# MCU.net
KiCad netlist of a schematic drawn in Altium Designer
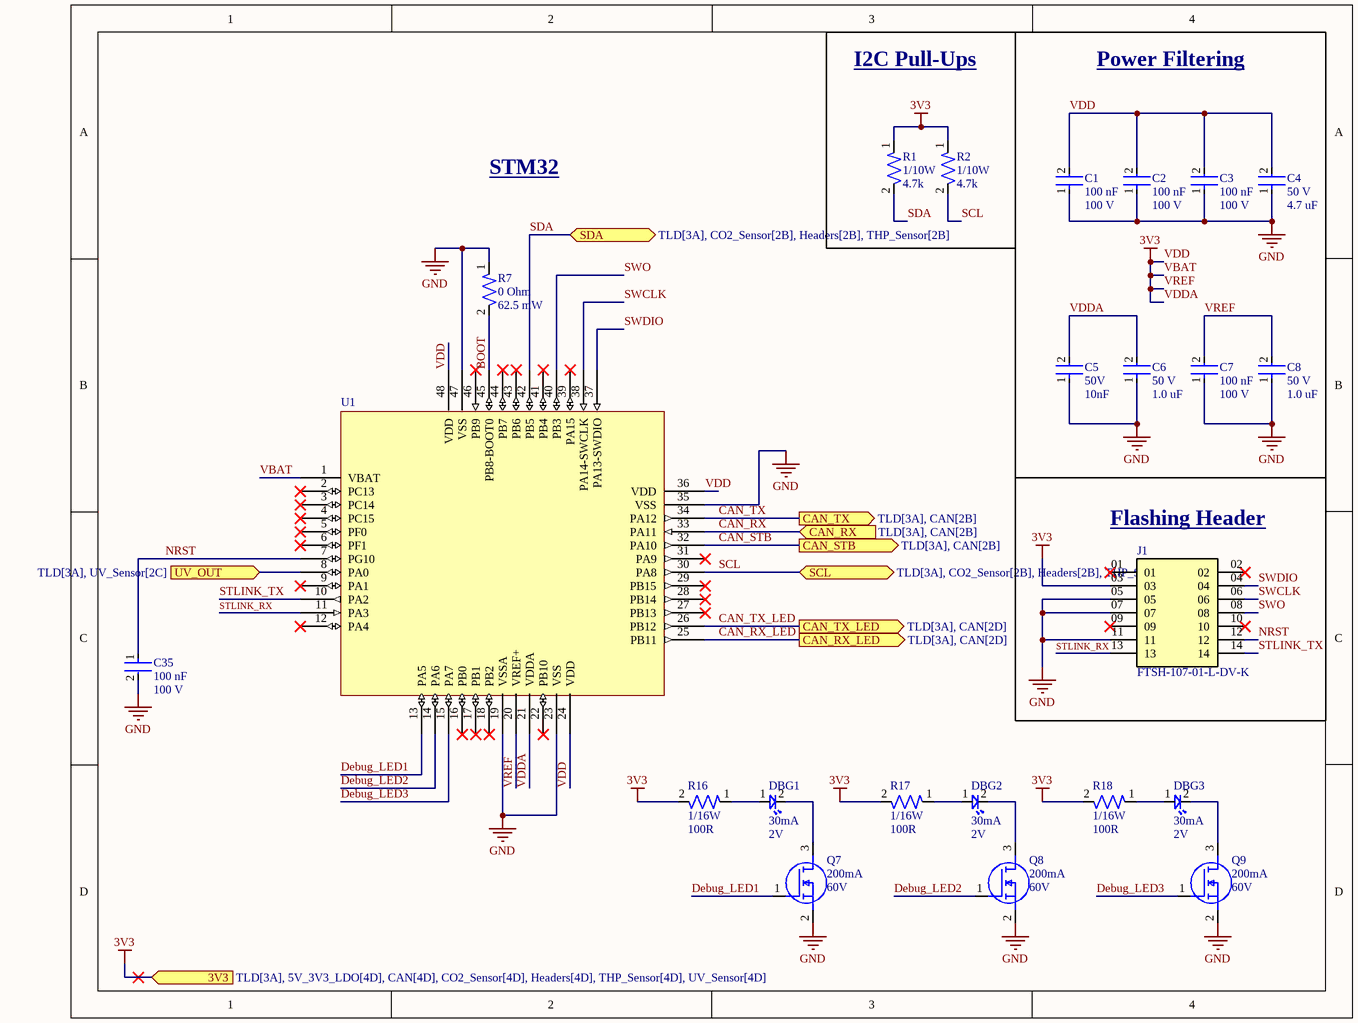
[diagram p0: MCU.SchDoc]

(export (version "E")
  (design (tool "Eeschema 10.0.6"))
  (components
    (comp (ref "C1")
      (value "CC0603KRX7R0BB104")
      (footprint "CAP-0603")
      (description "CAP CER 0.1UF 100V X7R 0603")
      (fields (field (name "CAPACITANCE") "100 nF") (field (name "VOLTAGE") "100 V"))
      (libsource (lib "JLC_25") (part "CAP-100N-0001"))
    )
    (comp (ref "C2")
      (value "CC0603KRX7R0BB104")
      (footprint "CAP-0603")
      (description "CAP CER 0.1UF 100V X7R 0603")
      (fields (field (name "CAPACITANCE") "100 nF") (field (name "VOLTAGE") "100 V"))
      (libsource (lib "JLC_25") (part "CAP-100N-0001"))
    )
    (comp (ref "C3")
      (value "CC0603KRX7R0BB104")
      (footprint "CAP-0603")
      (description "CAP CER 0.1UF 100V X7R 0603")
      (fields (field (name "CAPACITANCE") "100 nF") (field (name "VOLTAGE") "100 V"))
      (libsource (lib "JLC_25") (part "CAP-100N-0001"))
    )
    (comp (ref "C4")
      (value "CC0805KKX5R9BB475")
      (footprint "CAP-0805")
      (description "CAP CER 4.7UF 50V X5R 0805")
      (fields (field (name "VOLTAGE") "50 V") (field (name "CAPACITANCE") "4.7 uF"))
      (libsource (lib "JLC_25") (part "CAP-4.7U-0002"))
    )
    (comp (ref "C5")
      (value "GRM2195C1H103JA01D")
      (footprint "CAP-0805")
      (description "CAP CER 10000PF 50V C0G/NP0 0805")
      (fields (field (name "VOLTAGE") "50V") (field (name "CAPACITANCE") "10nF"))
      (libsource (lib "JLC_25") (part "CAP-10N-0001"))
    )
    (comp (ref "C6")
      (value "CC0805KKX7R9BB105")
      (footprint "CAP-0805")
      (description "CAP CER 1UF 50V X7R 0805")
      (fields (field (name "VOLTAGE") "50 V") (field (name "CAPACITANCE") "1.0 uF"))
      (libsource (lib "JLC_25") (part "CAP-1U-0001"))
    )
    (comp (ref "C7")
      (value "CC0603KRX7R0BB104")
      (footprint "CAP-0603")
      (description "CAP CER 0.1UF 100V X7R 0603")
      (fields (field (name "CAPACITANCE") "100 nF") (field (name "VOLTAGE") "100 V"))
      (libsource (lib "JLC_25") (part "CAP-100N-0001"))
    )
    (comp (ref "C8")
      (value "CC0805KKX7R9BB105")
      (footprint "CAP-0805")
      (description "CAP CER 1UF 50V X7R 0805")
      (fields (field (name "VOLTAGE") "50 V") (field (name "CAPACITANCE") "1.0 uF"))
      (libsource (lib "JLC_25") (part "CAP-1U-0001"))
    )
    (comp (ref "C35")
      (value "CC0603KRX7R0BB104")
      (footprint "CAP-0603")
      (description "CAP CER 0.1UF 100V X7R 0603")
      (fields (field (name "CAPACITANCE") "100 nF") (field (name "VOLTAGE") "100 V"))
      (libsource (lib "JLC_25") (part "CAP-100N-0001"))
    )
    (comp (ref "DBG1")
      (value "BL-HKC36G-AV-TRB")
      (footprint "LED-0603")
      (description "LED YELLOW CLEAR 0603 SMD")
      (fields (field (name "FORWARD CURRENT") "30mA") (field (name "FORWARD VOLTAGE") "2V"))
      (libsource (lib "JLC_25") (part "LED-0001"))
    )
    (comp (ref "DBG2")
      (value "BL-HKC36G-AV-TRB")
      (footprint "LED-0603")
      (description "LED YELLOW CLEAR 0603 SMD")
      (fields (field (name "FORWARD CURRENT") "30mA") (field (name "FORWARD VOLTAGE") "2V"))
      (libsource (lib "JLC_25") (part "LED-0001"))
    )
    (comp (ref "DBG3")
      (value "BL-HKC36G-AV-TRB")
      (footprint "LED-0603")
      (description "LED YELLOW CLEAR 0603 SMD")
      (fields (field (name "FORWARD CURRENT") "30mA") (field (name "FORWARD VOLTAGE") "2V"))
      (libsource (lib "JLC_25") (part "LED-0001"))
    )
    (comp (ref "J1")
      (value "FTSH-107-01-L-DV-K")
      (footprint "SAMTEC_FTSH-107-01-L-DV-K")
      (description "Connector Header Surface Mount 14 position 0.050\" (1.27mm)")
      (fields (field (name "MF") "Samtec"))
      (libsource (lib "MasterLib") (part "CONN_Flashing-0001"))
    )
    (comp (ref "Q7")
      (value "T2N7002AK,LM")
      (footprint "IC-SOT23-3")
      (description "MOSFET N-CH 60V 200MA SOT23")
      (fields (field (name "CONTINUOUS CURRENT") "200mA") (field (name "VOLTAGE") "60V"))
      (libsource (lib "JLC_25") (part "NMOS-200MA-0001"))
    )
    (comp (ref "Q8")
      (value "T2N7002AK,LM")
      (footprint "IC-SOT23-3")
      (description "MOSFET N-CH 60V 200MA SOT23")
      (fields (field (name "CONTINUOUS CURRENT") "200mA") (field (name "VOLTAGE") "60V"))
      (libsource (lib "JLC_25") (part "NMOS-200MA-0001"))
    )
    (comp (ref "Q9")
      (value "T2N7002AK,LM")
      (footprint "IC-SOT23-3")
      (description "MOSFET N-CH 60V 200MA SOT23")
      (fields (field (name "CONTINUOUS CURRENT") "200mA") (field (name "VOLTAGE") "60V"))
      (libsource (lib "JLC_25") (part "NMOS-200MA-0001"))
    )
    (comp (ref "R1")
      (value "RC0603FR-074K7L")
      (footprint "RES-0603")
      (description "RES 4.7K OHM 1% 1/10W 0603")
      (fields
        (field (name "TOLERANCE") "1%")
        (field (name "POWER") "1/10W")
        (field (name "RESISTANCE") "4.7k")
      )
      (libsource (lib "JLC_25") (part "RES-4.7k-0001"))
    )
    (comp (ref "R2")
      (value "RC0603FR-074K7L")
      (footprint "RES-0603")
      (description "RES 4.7K OHM 1% 1/10W 0603")
      (fields
        (field (name "TOLERANCE") "1%")
        (field (name "POWER") "1/10W")
        (field (name "RESISTANCE") "4.7k")
      )
      (libsource (lib "JLC_25") (part "RES-4.7k-0001"))
    )
    (comp (ref "R7")
      (value "RC0402FR-070RL")
      (footprint "RES-0402")
      (description "62.5mW Thick Film Resistors 50V -55℃~+155℃ 0Ω 0402 Chip Resistor - Surface Mount ROHS")
      (fields
        (field (name "JLC PART NUMBER") "C106231")
        (field (name "RESISTANCE") "0 Ohm")
        (field (name "POWER") "62.5 mW")
      )
      (libsource (lib "MasterLib") (part "RES-0-0002-JLC"))
    )
    (comp (ref "R16")
      (value "RC0402FR-07100RL")
      (footprint "RES-0402")
      (description "RES 100 OHM 1% 1/16W 0402")
      (fields
        (field (name "TOLERANCE") "1%")
        (field (name "POWER") "1/16W")
        (field (name "RESISTANCE") "100R")
      )
      (libsource (lib "JLC_25") (part "RES-100-0001"))
    )
    (comp (ref "R17")
      (value "RC0402FR-07100RL")
      (footprint "RES-0402")
      (description "RES 100 OHM 1% 1/16W 0402")
      (fields
        (field (name "TOLERANCE") "1%")
        (field (name "POWER") "1/16W")
        (field (name "RESISTANCE") "100R")
      )
      (libsource (lib "JLC_25") (part "RES-100-0001"))
    )
    (comp (ref "R18")
      (value "RC0402FR-07100RL")
      (footprint "RES-0402")
      (description "RES 100 OHM 1% 1/16W 0402")
      (fields
        (field (name "TOLERANCE") "1%")
        (field (name "POWER") "1/16W")
        (field (name "RESISTANCE") "100R")
      )
      (libsource (lib "JLC_25") (part "RES-100-0001"))
    )
    (comp (ref "U1")
      (value "STM32G431CBT6")
      (footprint "IC-LQFP48")
      (description "IC MCU 32BIT 128KB FLASH 48LQFP")
      (libsource (lib "JLC_25") (part "IC-STM32G431CBT6"))
    )
  )
  (nets
    (net (code "1") (name "/BOOT") (class "Default")
      (node (ref "R7") (pin "2") (pinfunction "2_2") (pintype "passive"))
      (node (ref "U1") (pin "45") (pinfunction "PB8-BOOT0_45") (pintype "bidirectional"))
    )
    (net (code "2") (name "/CAN_RX") (class "Default")
      (node (ref "U1") (pin "33") (pinfunction "PA11_33") (pintype "input"))
    )
    (net (code "3") (name "/CAN_RX_LED") (class "Default")
      (node (ref "U1") (pin "25") (pinfunction "PB11_25") (pintype "output"))
    )
    (net (code "4") (name "/CAN_STB") (class "Default")
      (node (ref "U1") (pin "32") (pinfunction "PA10_32") (pintype "output"))
    )
    (net (code "5") (name "/CAN_TX") (class "Default")
      (node (ref "U1") (pin "34") (pinfunction "PA12_34") (pintype "output"))
    )
    (net (code "6") (name "/CAN_TX_LED") (class "Default")
      (node (ref "U1") (pin "26") (pinfunction "PB12_26") (pintype "output"))
    )
    (net (code "7") (name "/Debug_LED1") (class "Default")
      (node (ref "Q7") (pin "1") (pinfunction "G_1") (pintype "passive"))
      (node (ref "U1") (pin "13") (pinfunction "PA5_13") (pintype "bidirectional"))
    )
    (net (code "8") (name "/Debug_LED2") (class "Default")
      (node (ref "Q8") (pin "1") (pinfunction "G_1") (pintype "passive"))
      (node (ref "U1") (pin "14") (pinfunction "PA6_14") (pintype "bidirectional"))
    )
    (net (code "9") (name "/Debug_LED3") (class "Default")
      (node (ref "Q9") (pin "1") (pinfunction "G_1") (pintype "passive"))
      (node (ref "U1") (pin "15") (pinfunction "PA7_15") (pintype "bidirectional"))
    )
    (net (code "10") (name "/NRST") (class "Default")
      (node (ref "C35") (pin "1") (pinfunction "1_1") (pintype "passive"))
      (node (ref "J1") (pin "12") (pinfunction "12_12") (pintype "passive"))
      (node (ref "U1") (pin "7") (pinfunction "PG10_7") (pintype "bidirectional"))
    )
    (net (code "11") (name "/SCL") (class "Default")
      (node (ref "R2") (pin "2") (pinfunction "2_2") (pintype "passive"))
      (node (ref "U1") (pin "30") (pinfunction "PA8_30") (pintype "output"))
    )
    (net (code "12") (name "/SDA") (class "Default")
      (node (ref "R1") (pin "2") (pinfunction "2_2") (pintype "passive"))
      (node (ref "U1") (pin "42") (pinfunction "PB5_42") (pintype "bidirectional"))
    )
    (net (code "13") (name "/STLINK_RX") (class "Default")
      (node (ref "J1") (pin "13") (pinfunction "13_13") (pintype "passive"))
      (node (ref "U1") (pin "11") (pinfunction "PA3_11") (pintype "input"))
    )
    (net (code "14") (name "/STLINK_TX") (class "Default")
      (node (ref "J1") (pin "14") (pinfunction "14_14") (pintype "passive"))
      (node (ref "U1") (pin "10") (pinfunction "PA2_10") (pintype "output"))
    )
    (net (code "15") (name "/SWCLK") (class "Default")
      (node (ref "J1") (pin "06") (pinfunction "06_06") (pintype "passive"))
      (node (ref "U1") (pin "38") (pinfunction "PA14-SWCLK_38") (pintype "input"))
    )
    (net (code "16") (name "/SWDIO") (class "Default")
      (node (ref "J1") (pin "04") (pinfunction "04_04") (pintype "passive"))
      (node (ref "U1") (pin "37") (pinfunction "PA13-SWDIO_37") (pintype "input"))
    )
    (net (code "17") (name "/SWO") (class "Default")
      (node (ref "J1") (pin "08") (pinfunction "08_08") (pintype "passive"))
      (node (ref "U1") (pin "40") (pinfunction "PB3_40") (pintype "bidirectional"))
    )
    (net (code "18") (name "/UV_OUT") (class "Default")
      (node (ref "U1") (pin "8") (pinfunction "PA0_8") (pintype "bidirectional"))
    )
    (net (code "19") (name "3V3") (class "Default")
      (node (ref "C1") (pin "2") (pinfunction "2_2") (pintype "passive"))
      (node (ref "C2") (pin "2") (pinfunction "2_2") (pintype "passive"))
      (node (ref "C3") (pin "2") (pinfunction "2_2") (pintype "passive"))
      (node (ref "C4") (pin "2") (pinfunction "2_2") (pintype "passive"))
      (node (ref "C5") (pin "2") (pinfunction "2_2") (pintype "passive"))
      (node (ref "C6") (pin "2") (pinfunction "2_2") (pintype "passive"))
      (node (ref "C7") (pin "2") (pinfunction "2_2") (pintype "passive"))
      (node (ref "C8") (pin "2") (pinfunction "2_2") (pintype "passive"))
      (node (ref "J1") (pin "03") (pinfunction "03_03") (pintype "passive"))
      (node (ref "R1") (pin "1") (pinfunction "1_1") (pintype "passive"))
      (node (ref "R16") (pin "2") (pinfunction "2_2") (pintype "passive"))
      (node (ref "R17") (pin "2") (pinfunction "2_2") (pintype "passive"))
      (node (ref "R18") (pin "2") (pinfunction "2_2") (pintype "passive"))
      (node (ref "R2") (pin "1") (pinfunction "1_1") (pintype "passive"))
      (node (ref "U1") (pin "1") (pinfunction "VBAT_1") (pintype "power_in"))
      (node (ref "U1") (pin "20") (pinfunction "VREF+_20") (pintype "power_in"))
      (node (ref "U1") (pin "21") (pinfunction "VDDA_21") (pintype "power_in"))
      (node (ref "U1") (pin "24") (pinfunction "VDD_24") (pintype "power_in"))
      (node (ref "U1") (pin "36") (pinfunction "VDD_36") (pintype "power_in"))
      (node (ref "U1") (pin "48") (pinfunction "VDD_48") (pintype "power_in"))
    )
    (net (code "20") (name "GND") (class "Default")
      (node (ref "C1") (pin "1") (pinfunction "1_1") (pintype "passive"))
      (node (ref "C2") (pin "1") (pinfunction "1_1") (pintype "passive"))
      (node (ref "C3") (pin "1") (pinfunction "1_1") (pintype "passive"))
      (node (ref "C35") (pin "2") (pinfunction "2_2") (pintype "passive"))
      (node (ref "C4") (pin "1") (pinfunction "1_1") (pintype "passive"))
      (node (ref "C5") (pin "1") (pinfunction "1_1") (pintype "passive"))
      (node (ref "C6") (pin "1") (pinfunction "1_1") (pintype "passive"))
      (node (ref "C7") (pin "1") (pinfunction "1_1") (pintype "passive"))
      (node (ref "C8") (pin "1") (pinfunction "1_1") (pintype "passive"))
      (node (ref "J1") (pin "05") (pinfunction "05_05") (pintype "passive"))
      (node (ref "J1") (pin "07") (pinfunction "07_07") (pintype "passive"))
      (node (ref "J1") (pin "11") (pinfunction "11_11") (pintype "passive"))
      (node (ref "Q7") (pin "2") (pinfunction "S_2") (pintype "passive"))
      (node (ref "Q8") (pin "2") (pinfunction "S_2") (pintype "passive"))
      (node (ref "Q9") (pin "2") (pinfunction "S_2") (pintype "passive"))
      (node (ref "R7") (pin "1") (pinfunction "1_1") (pintype "passive"))
      (node (ref "U1") (pin "19") (pinfunction "VSSA_19") (pintype "power_in"))
      (node (ref "U1") (pin "23") (pinfunction "VSS_23") (pintype "power_in"))
      (node (ref "U1") (pin "35") (pinfunction "VSS_35") (pintype "power_in"))
      (node (ref "U1") (pin "47") (pinfunction "VSS_47") (pintype "power_in"))
    )
    (net (code "21") (name "Net-(DBG1-Pad1)") (class "Default")
      (node (ref "DBG1") (pin "1") (pinfunction "1_1") (pintype "passive"))
      (node (ref "R16") (pin "1") (pinfunction "1_1") (pintype "passive"))
    )
    (net (code "22") (name "Net-(DBG2-Pad1)") (class "Default")
      (node (ref "DBG2") (pin "1") (pinfunction "1_1") (pintype "passive"))
      (node (ref "R17") (pin "1") (pinfunction "1_1") (pintype "passive"))
    )
    (net (code "23") (name "Net-(DBG3-Pad1)") (class "Default")
      (node (ref "DBG3") (pin "1") (pinfunction "1_1") (pintype "passive"))
      (node (ref "R18") (pin "1") (pinfunction "1_1") (pintype "passive"))
    )
    (net (code "24") (name "Net-(Q7-D)") (class "Default")
      (node (ref "DBG1") (pin "2") (pinfunction "2_2") (pintype "passive"))
      (node (ref "Q7") (pin "3") (pinfunction "D_3") (pintype "passive"))
    )
    (net (code "25") (name "Net-(Q8-D)") (class "Default")
      (node (ref "DBG2") (pin "2") (pinfunction "2_2") (pintype "passive"))
      (node (ref "Q8") (pin "3") (pinfunction "D_3") (pintype "passive"))
    )
    (net (code "26") (name "Net-(Q9-D)") (class "Default")
      (node (ref "DBG3") (pin "2") (pinfunction "2_2") (pintype "passive"))
      (node (ref "Q9") (pin "3") (pinfunction "D_3") (pintype "passive"))
    )
    (net (code "27") (name "unconnected-(J1-Pad01)") (class "Default")
      (node (ref "J1") (pin "01") (pinfunction "01_01") (pintype "passive+no_connect"))
    )
    (net (code "28") (name "unconnected-(J1-Pad02)") (class "Default")
      (node (ref "J1") (pin "02") (pinfunction "02_02") (pintype "passive+no_connect"))
    )
    (net (code "29") (name "unconnected-(J1-Pad09)") (class "Default")
      (node (ref "J1") (pin "09") (pinfunction "09_09") (pintype "passive+no_connect"))
    )
    (net (code "30") (name "unconnected-(J1-Pad10)") (class "Default")
      (node (ref "J1") (pin "10") (pinfunction "10_10") (pintype "passive+no_connect"))
    )
    (net (code "31") (name "unconnected-(U1-PA1-Pad9)") (class "Default")
      (node (ref "U1") (pin "9") (pinfunction "PA1_9") (pintype "bidirectional+no_connect"))
    )
    (net (code "32") (name "unconnected-(U1-PA4-Pad12)") (class "Default")
      (node (ref "U1") (pin "12") (pinfunction "PA4_12") (pintype "bidirectional+no_connect"))
    )
    (net (code "33") (name "unconnected-(U1-PA9-Pad31)") (class "Default")
      (node (ref "U1") (pin "31") (pinfunction "PA9_31") (pintype "output+no_connect"))
    )
    (net (code "34") (name "unconnected-(U1-PA15-Pad39)") (class "Default")
      (node (ref "U1") (pin "39") (pinfunction "PA15_39") (pintype "bidirectional+no_connect"))
    )
    (net (code "35") (name "unconnected-(U1-PB0-Pad16)") (class "Default")
      (node (ref "U1") (pin "16") (pinfunction "PB0_16") (pintype "bidirectional+no_connect"))
    )
    (net (code "36") (name "unconnected-(U1-PB1-Pad17)") (class "Default")
      (node (ref "U1") (pin "17") (pinfunction "PB1_17") (pintype "bidirectional+no_connect"))
    )
    (net (code "37") (name "unconnected-(U1-PB2-Pad18)") (class "Default")
      (node (ref "U1") (pin "18") (pinfunction "PB2_18") (pintype "bidirectional+no_connect"))
    )
    (net (code "38") (name "unconnected-(U1-PB4-Pad41)") (class "Default")
      (node (ref "U1") (pin "41") (pinfunction "PB4_41") (pintype "bidirectional+no_connect"))
    )
    (net (code "39") (name "unconnected-(U1-PB6-Pad43)") (class "Default")
      (node (ref "U1") (pin "43") (pinfunction "PB6_43") (pintype "bidirectional+no_connect"))
    )
    (net (code "40") (name "unconnected-(U1-PB7-Pad44)") (class "Default")
      (node (ref "U1") (pin "44") (pinfunction "PB7_44") (pintype "bidirectional+no_connect"))
    )
    (net (code "41") (name "unconnected-(U1-PB9-Pad46)") (class "Default")
      (node (ref "U1") (pin "46") (pinfunction "PB9_46") (pintype "input+no_connect"))
    )
    (net (code "42") (name "unconnected-(U1-PB10-Pad22)") (class "Default")
      (node (ref "U1") (pin "22") (pinfunction "PB10_22") (pintype "bidirectional+no_connect"))
    )
    (net (code "43") (name "unconnected-(U1-PB13-Pad27)") (class "Default")
      (node (ref "U1") (pin "27") (pinfunction "PB13_27") (pintype "output+no_connect"))
    )
    (net (code "44") (name "unconnected-(U1-PB14-Pad28)") (class "Default")
      (node (ref "U1") (pin "28") (pinfunction "PB14_28") (pintype "output+no_connect"))
    )
    (net (code "45") (name "unconnected-(U1-PB15-Pad29)") (class "Default")
      (node (ref "U1") (pin "29") (pinfunction "PB15_29") (pintype "output+no_connect"))
    )
    (net (code "46") (name "unconnected-(U1-PC13-Pad2)") (class "Default")
      (node (ref "U1") (pin "2") (pinfunction "PC13_2") (pintype "bidirectional+no_connect"))
    )
    (net (code "47") (name "unconnected-(U1-PC14-Pad3)") (class "Default")
      (node (ref "U1") (pin "3") (pinfunction "PC14_3") (pintype "bidirectional+no_connect"))
    )
    (net (code "48") (name "unconnected-(U1-PC15-Pad4)") (class "Default")
      (node (ref "U1") (pin "4") (pinfunction "PC15_4") (pintype "bidirectional+no_connect"))
    )
    (net (code "49") (name "unconnected-(U1-PF0-Pad5)") (class "Default")
      (node (ref "U1") (pin "5") (pinfunction "PF0_5") (pintype "bidirectional+no_connect"))
    )
    (net (code "50") (name "unconnected-(U1-PF1-Pad6)") (class "Default")
      (node (ref "U1") (pin "6") (pinfunction "PF1_6") (pintype "bidirectional+no_connect"))
    )
  )
)
